# radiosonde_lite_final.net
KiCad netlist of a schematic drawn in EAGLE
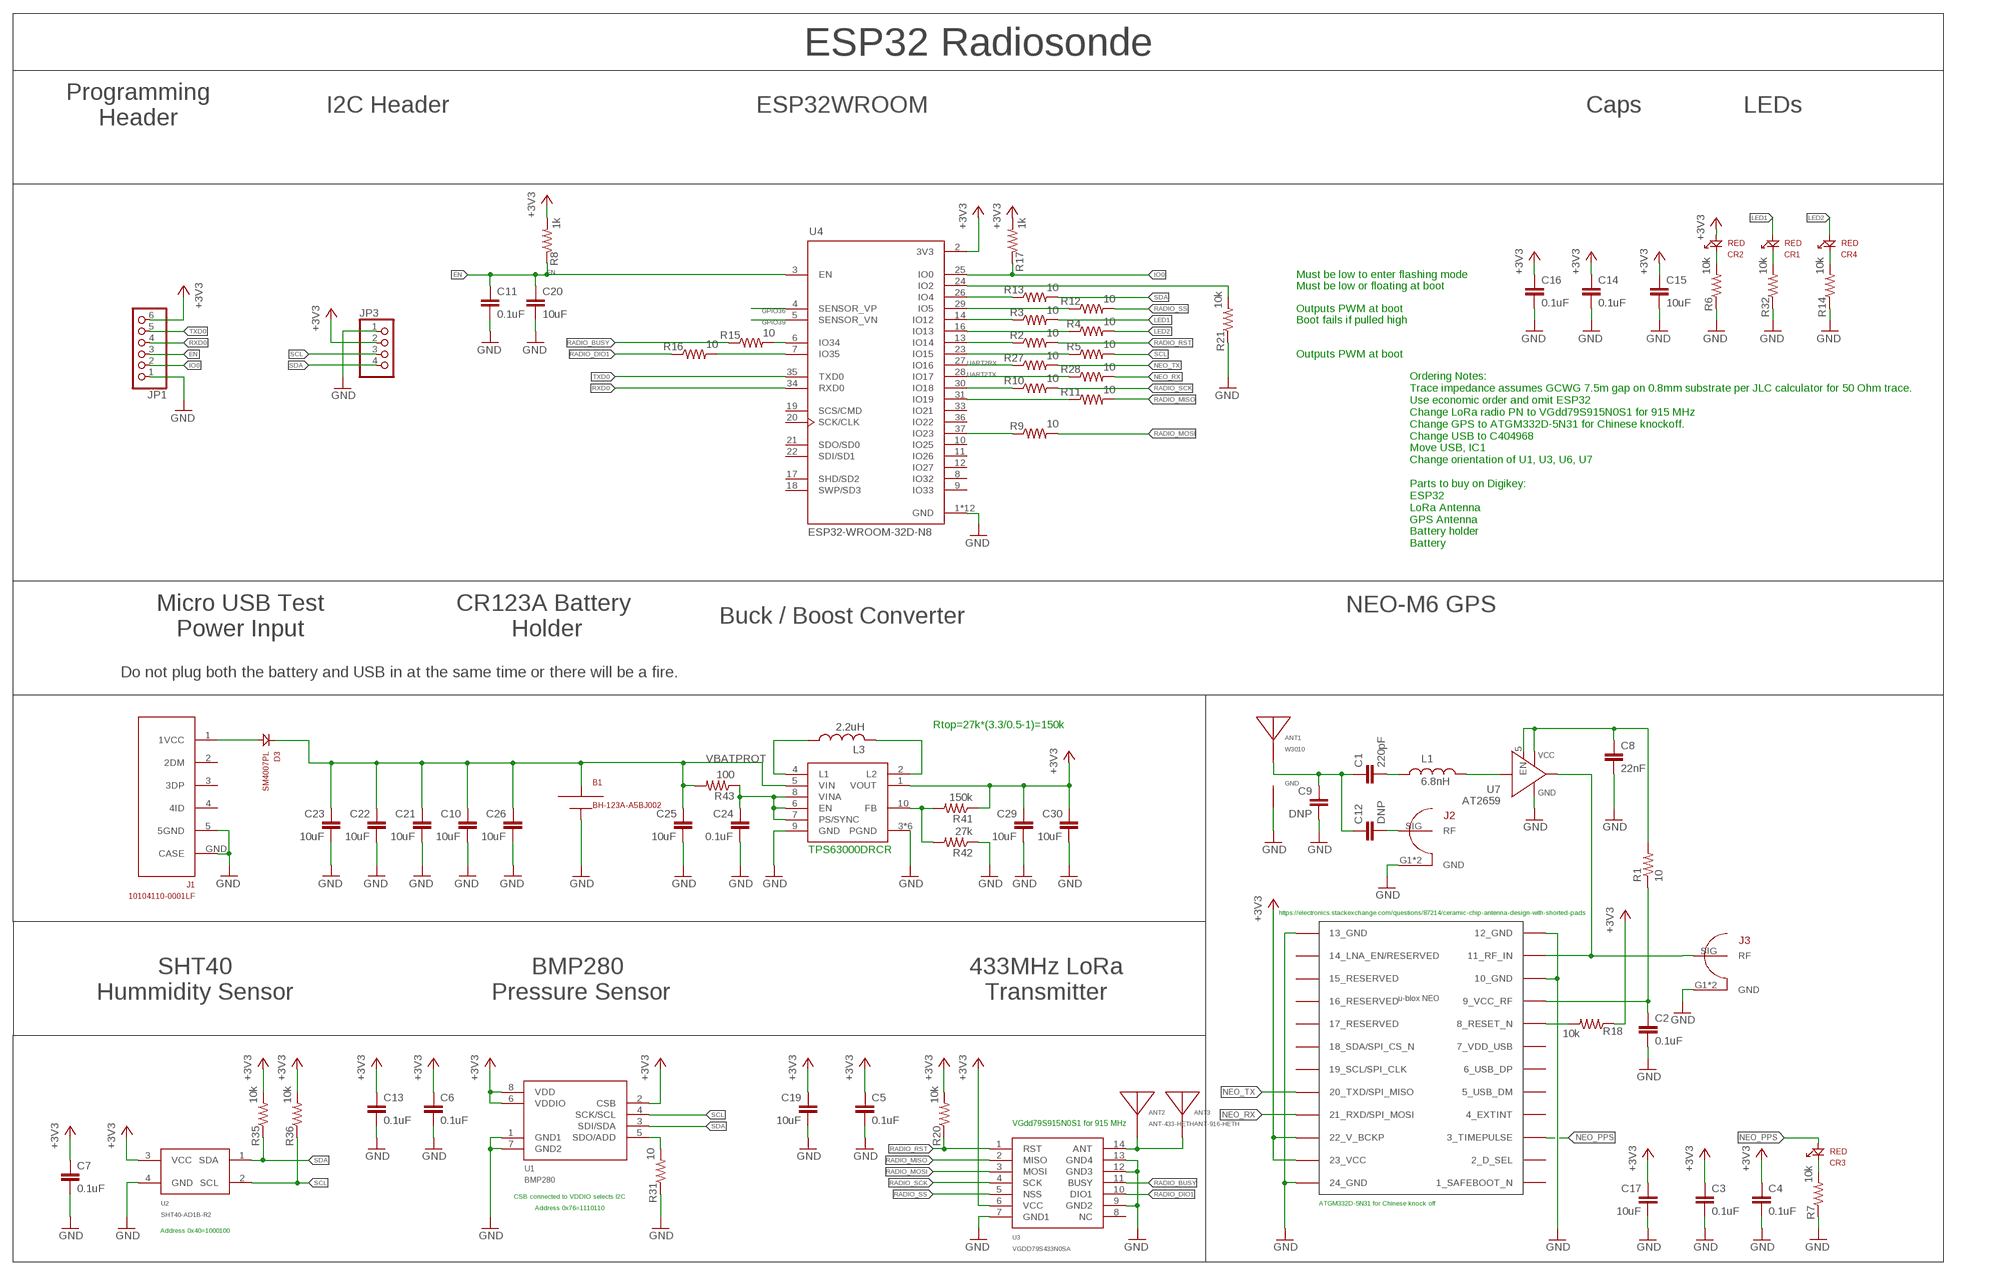
[diagram p0: schematic, sheet 1]

(export (version "E")
  (design (tool "Eeschema 10.0.6"))
  (components
    (comp (ref "ANT1")
      (value "W3010")
      (footprint "eagle-import:W3010")
      (libsource (lib "eagle-import") (part "W3010"))
    )
    (comp (ref "ANT2")
      (value "ANT-433-HETH")
      (footprint "eagle-import:ANT-433-HETH")
      (fields (field (name "PARTNO") "ANT-433-HETH-ND"))
      (libsource (lib "eagle-import") (part "ANT-433-HETH"))
    )
    (comp (ref "ANT3")
      (value "ANT-916-HETH")
      (footprint "eagle-import:ANT-916-HETH")
      (libsource (lib "eagle-import") (part "ANT-916-HETH"))
    )
    (comp (ref "B1")
      (value "BH-123A-A5BJ002")
      (footprint "eagle-import:BH-123A-A5BJ002")
      (libsource (lib "eagle-import") (part "BH-123A-A5BJ002"))
    )
    (comp (ref "C1")
      (value "220pF")
      (footprint "eagle-import:0402_INDUCTOR")
      (libsource (lib "eagle-import") (part "0402_CAPACITOR"))
    )
    (comp (ref "C2")
      (value "0.1uF")
      (footprint "eagle-import:0402_INDUCTOR")
      (libsource (lib "eagle-import") (part "0402_CAPACITOR"))
    )
    (comp (ref "C3")
      (value "0.1uF")
      (footprint "eagle-import:0402_INDUCTOR")
      (libsource (lib "eagle-import") (part "0402_CAPACITOR"))
    )
    (comp (ref "C4")
      (value "0.1uF")
      (footprint "eagle-import:0402_INDUCTOR")
      (libsource (lib "eagle-import") (part "0402_CAPACITOR"))
    )
    (comp (ref "C5")
      (value "0.1uF")
      (footprint "eagle-import:0402_INDUCTOR")
      (libsource (lib "eagle-import") (part "0402_CAPACITOR"))
    )
    (comp (ref "C6")
      (value "0.1uF")
      (footprint "eagle-import:0402_INDUCTOR")
      (libsource (lib "eagle-import") (part "0402_CAPACITOR"))
    )
    (comp (ref "C7")
      (value "0.1uF")
      (footprint "eagle-import:0402_INDUCTOR")
      (libsource (lib "eagle-import") (part "0402_CAPACITOR"))
    )
    (comp (ref "C8")
      (value "22nF")
      (footprint "eagle-import:0402_INDUCTOR")
      (libsource (lib "eagle-import") (part "0402_CAPACITOR"))
    )
    (comp (ref "C9")
      (value "DNP")
      (footprint "eagle-import:0402_INDUCTOR")
      (libsource (lib "eagle-import") (part "0402_CAPACITOR"))
    )
    (comp (ref "C10")
      (value "10uF")
      (footprint "eagle-import:0603")
      (libsource (lib "eagle-import") (part "0603_CAPACITOR"))
    )
    (comp (ref "C11")
      (value "0.1uF")
      (footprint "eagle-import:0402_INDUCTOR")
      (libsource (lib "eagle-import") (part "0402_CAPACITOR"))
    )
    (comp (ref "C12")
      (value "DNP")
      (footprint "eagle-import:0402_INDUCTOR")
      (libsource (lib "eagle-import") (part "0402_CAPACITOR"))
    )
    (comp (ref "C13")
      (value "0.1uF")
      (footprint "eagle-import:0402_INDUCTOR")
      (libsource (lib "eagle-import") (part "0402_CAPACITOR"))
    )
    (comp (ref "C14")
      (value "0.1uF")
      (footprint "eagle-import:0402_INDUCTOR")
      (libsource (lib "eagle-import") (part "0402_CAPACITOR"))
    )
    (comp (ref "C15")
      (value "10uF")
      (footprint "eagle-import:0603")
      (libsource (lib "eagle-import") (part "0603_CAPACITOR"))
    )
    (comp (ref "C16")
      (value "0.1uF")
      (footprint "eagle-import:0402_INDUCTOR")
      (libsource (lib "eagle-import") (part "0402_CAPACITOR"))
    )
    (comp (ref "C17")
      (value "10uF")
      (footprint "eagle-import:0603")
      (libsource (lib "eagle-import") (part "0603_CAPACITOR"))
    )
    (comp (ref "C19")
      (value "10uF")
      (footprint "eagle-import:0603")
      (libsource (lib "eagle-import") (part "0603_CAPACITOR"))
    )
    (comp (ref "C20")
      (value "10uF")
      (footprint "eagle-import:0603")
      (libsource (lib "eagle-import") (part "0603_CAPACITOR"))
    )
    (comp (ref "C21")
      (value "10uF")
      (footprint "eagle-import:0603")
      (libsource (lib "eagle-import") (part "0603_CAPACITOR"))
    )
    (comp (ref "C22")
      (value "10uF")
      (footprint "eagle-import:0603")
      (libsource (lib "eagle-import") (part "0603_CAPACITOR"))
    )
    (comp (ref "C23")
      (value "10uF")
      (footprint "eagle-import:0603")
      (libsource (lib "eagle-import") (part "0603_CAPACITOR"))
    )
    (comp (ref "C24")
      (value "0.1uF")
      (footprint "eagle-import:0603")
      (libsource (lib "eagle-import") (part "0603_CAPACITOR"))
    )
    (comp (ref "C25")
      (value "10uF")
      (footprint "eagle-import:0603")
      (libsource (lib "eagle-import") (part "0603_CAPACITOR"))
    )
    (comp (ref "C26")
      (value "10uF")
      (footprint "eagle-import:0603")
      (libsource (lib "eagle-import") (part "0603_CAPACITOR"))
    )
    (comp (ref "C29")
      (value "10uF")
      (footprint "eagle-import:0603")
      (libsource (lib "eagle-import") (part "0603_CAPACITOR"))
    )
    (comp (ref "C30")
      (value "10uF")
      (footprint "eagle-import:0603")
      (libsource (lib "eagle-import") (part "0603_CAPACITOR"))
    )
    (comp (ref "CR1")
      (value "RED")
      (footprint "eagle-import:0603_DIODE")
      (fields (field (name "PARTNO") "732-4978-1-ND"))
      (libsource (lib "eagle-import") (part "150060RS75000"))
    )
    (comp (ref "CR2")
      (value "RED")
      (footprint "eagle-import:0603_DIODE")
      (fields (field (name "PARTNO") "732-4978-1-ND"))
      (libsource (lib "eagle-import") (part "150060RS75000"))
    )
    (comp (ref "CR3")
      (value "RED")
      (footprint "eagle-import:0603_DIODE")
      (fields (field (name "PARTNO") "732-4978-1-ND"))
      (libsource (lib "eagle-import") (part "150060RS75000"))
    )
    (comp (ref "CR4")
      (value "RED")
      (footprint "eagle-import:0603_DIODE")
      (fields (field (name "PARTNO") "732-4978-1-ND"))
      (libsource (lib "eagle-import") (part "150060RS75000"))
    )
    (comp (ref "D3")
      (value "SM4007PL")
      (footprint "eagle-import:SOD123(AK)")
      (libsource (lib "eagle-import") (part "SM4007PL"))
    )
    (comp (ref "IC1")
      (value "NEO-M8")
      (footprint "eagle-import:NEO-M8")
      (libsource (lib "eagle-import") (part "NEO-M8"))
    )
    (comp (ref "J1")
      (value "10104110-0001LF")
      (footprint "eagle-import:MICRO_USB")
      (fields (field (name "PARTNO") "609-4052-1-ND"))
      (libsource (lib "eagle-import") (part "10104110-0001LF"))
    )
    (comp (ref "J2")
      (value "CONUFL001-SMD")
      (footprint "eagle-import:U.FL")
      (libsource (lib "eagle-import") (part "CONUFL001-SMD"))
    )
    (comp (ref "J3")
      (value "CONUFL001-SMD")
      (footprint "eagle-import:U.FL")
      (libsource (lib "eagle-import") (part "CONUFL001-SMD"))
    )
    (comp (ref "JP1")
      (value "PINHD-1X6")
      (footprint "eagle-import:1X06")
      (libsource (lib "eagle-import") (part "PINHD-1X6"))
    )
    (comp (ref "JP3")
      (value "PINHD-1X4")
      (footprint "eagle-import:1X04")
      (libsource (lib "eagle-import") (part "PINHD-1X4"))
    )
    (comp (ref "L1")
      (value "6.8nH")
      (footprint "eagle-import:0402_INDUCTOR")
      (libsource (lib "eagle-import") (part "0402_INDUCTOR"))
    )
    (comp (ref "L3")
      (value "2.2uH")
      (footprint "eagle-import:CY43")
      (libsource (lib "eagle-import") (part "CY43-2.2UH"))
    )
    (comp (ref "R1")
      (value "10")
      (footprint "eagle-import:R0402")
      (libsource (lib "eagle-import") (part "0402_RESISTOR"))
    )
    (comp (ref "R2")
      (value "10")
      (footprint "eagle-import:R0402")
      (libsource (lib "eagle-import") (part "0402_RESISTOR"))
    )
    (comp (ref "R3")
      (value "10")
      (footprint "eagle-import:R0402")
      (libsource (lib "eagle-import") (part "0402_RESISTOR"))
    )
    (comp (ref "R4")
      (value "10")
      (footprint "eagle-import:R0402")
      (libsource (lib "eagle-import") (part "0402_RESISTOR"))
    )
    (comp (ref "R5")
      (value "10")
      (footprint "eagle-import:R0402")
      (libsource (lib "eagle-import") (part "0402_RESISTOR"))
    )
    (comp (ref "R6")
      (value "10k")
      (footprint "eagle-import:R0402")
      (libsource (lib "eagle-import") (part "0402_RESISTOR"))
    )
    (comp (ref "R7")
      (value "10k")
      (footprint "eagle-import:R0402")
      (libsource (lib "eagle-import") (part "0402_RESISTOR"))
    )
    (comp (ref "R8")
      (value "1k")
      (footprint "eagle-import:R0402")
      (libsource (lib "eagle-import") (part "0402_RESISTOR"))
    )
    (comp (ref "R9")
      (value "10")
      (footprint "eagle-import:R0402")
      (libsource (lib "eagle-import") (part "0402_RESISTOR"))
    )
    (comp (ref "R10")
      (value "10")
      (footprint "eagle-import:R0402")
      (libsource (lib "eagle-import") (part "0402_RESISTOR"))
    )
    (comp (ref "R11")
      (value "10")
      (footprint "eagle-import:R0402")
      (libsource (lib "eagle-import") (part "0402_RESISTOR"))
    )
    (comp (ref "R12")
      (value "10")
      (footprint "eagle-import:R0402")
      (libsource (lib "eagle-import") (part "0402_RESISTOR"))
    )
    (comp (ref "R13")
      (value "10")
      (footprint "eagle-import:R0402")
      (libsource (lib "eagle-import") (part "0402_RESISTOR"))
    )
    (comp (ref "R14")
      (value "10k")
      (footprint "eagle-import:R0402")
      (libsource (lib "eagle-import") (part "0402_RESISTOR"))
    )
    (comp (ref "R15")
      (value "10")
      (footprint "eagle-import:R0402")
      (libsource (lib "eagle-import") (part "0402_RESISTOR"))
    )
    (comp (ref "R16")
      (value "10")
      (footprint "eagle-import:R0402")
      (libsource (lib "eagle-import") (part "0402_RESISTOR"))
    )
    (comp (ref "R17")
      (value "1k")
      (footprint "eagle-import:R0402")
      (libsource (lib "eagle-import") (part "0402_RESISTOR"))
    )
    (comp (ref "R18")
      (value "10k")
      (footprint "eagle-import:R0402")
      (libsource (lib "eagle-import") (part "0402_RESISTOR"))
    )
    (comp (ref "R20")
      (value "10k")
      (footprint "eagle-import:R0402")
      (libsource (lib "eagle-import") (part "0402_RESISTOR"))
    )
    (comp (ref "R21")
      (value "10k")
      (footprint "eagle-import:R0402")
      (libsource (lib "eagle-import") (part "0402_RESISTOR"))
    )
    (comp (ref "R27")
      (value "10")
      (footprint "eagle-import:R0402")
      (libsource (lib "eagle-import") (part "0402_RESISTOR"))
    )
    (comp (ref "R28")
      (value "10")
      (footprint "eagle-import:R0402")
      (libsource (lib "eagle-import") (part "0402_RESISTOR"))
    )
    (comp (ref "R31")
      (value "10")
      (footprint "eagle-import:R0402")
      (libsource (lib "eagle-import") (part "0402_RESISTOR"))
    )
    (comp (ref "R32")
      (value "10k")
      (footprint "eagle-import:R0402")
      (libsource (lib "eagle-import") (part "0402_RESISTOR"))
    )
    (comp (ref "R35")
      (value "10k")
      (footprint "eagle-import:R0402")
      (libsource (lib "eagle-import") (part "0402_RESISTOR"))
    )
    (comp (ref "R36")
      (value "10k")
      (footprint "eagle-import:R0402")
      (libsource (lib "eagle-import") (part "0402_RESISTOR"))
    )
    (comp (ref "R41")
      (value "150k")
      (footprint "eagle-import:0603")
      (libsource (lib "eagle-import") (part "0603_RESISTOR"))
    )
    (comp (ref "R42")
      (value "27k")
      (footprint "eagle-import:0603")
      (libsource (lib "eagle-import") (part "0603_RESISTOR"))
    )
    (comp (ref "R43")
      (value "100")
      (footprint "eagle-import:0603")
      (libsource (lib "eagle-import") (part "0603_RESISTOR"))
    )
    (comp (ref "U1")
      (value "BMP280")
      (footprint "eagle-import:BME280")
      (fields (field (name "PARTNO") "828-1064-1-ND"))
      (libsource (lib "eagle-import") (part "BMP280"))
    )
    (comp (ref "U2")
      (value "SHT40-AD1B-R2")
      (footprint "eagle-import:SHT40")
      (libsource (lib "eagle-import") (part "SHT40-AD1B-R2"))
    )
    (comp (ref "U3")
      (value "VGDD79S433N0SA")
      (footprint "eagle-import:VGDD79S433N0SA")
      (libsource (lib "eagle-import") (part "VGDD79S433N0SA"))
    )
    (comp (ref "U4")
      (value "ESP32-WROOM-32D-N8")
      (footprint "eagle-import:MODULE_ESP32-WROOM-32D")
      (fields (field (name "MF") "Espressif Systems") (field (name "MP") "ESP32-WROOM-32D"))
      (libsource (lib "eagle-import") (part "ESP32-WROOM-32D"))
    )
    (comp (ref "U6")
      (value "TPS63000DRCR")
      (footprint "eagle-import:S-PVSON-N10")
      (fields (field (name "PARTNO") "296-19641-1-ND"))
      (libsource (lib "eagle-import") (part "TPS63000DRCR"))
    )
    (comp (ref "U7")
      (value "AT2659")
      (footprint "eagle-import:6DFN-1X1.6")
      (libsource (lib "eagle-import") (part "AT2659"))
    )
  )
  (nets
    (net (code "1") (name "+3V3") (class "Default")
      (node (ref "C13") (pin "P$1") (pinfunction "1_P$1") (pintype "passive"))
      (node (ref "C14") (pin "P$1") (pinfunction "1_P$1") (pintype "passive"))
      (node (ref "C15") (pin "1") (pinfunction "1_1") (pintype "passive"))
      (node (ref "C16") (pin "P$1") (pinfunction "1_P$1") (pintype "passive"))
      (node (ref "C17") (pin "1") (pinfunction "1_1") (pintype "passive"))
      (node (ref "C19") (pin "1") (pinfunction "1_1") (pintype "passive"))
      (node (ref "C29") (pin "1") (pinfunction "1_1") (pintype "passive"))
      (node (ref "C3") (pin "P$1") (pinfunction "1_P$1") (pintype "passive"))
      (node (ref "C30") (pin "1") (pinfunction "1_1") (pintype "passive"))
      (node (ref "C4") (pin "P$1") (pinfunction "1_P$1") (pintype "passive"))
      (node (ref "C5") (pin "P$1") (pinfunction "1_P$1") (pintype "passive"))
      (node (ref "C6") (pin "P$1") (pinfunction "1_P$1") (pintype "passive"))
      (node (ref "C7") (pin "P$1") (pinfunction "1_P$1") (pintype "passive"))
      (node (ref "CR2") (pin "A") (pinfunction "A_A") (pintype "bidirectional"))
      (node (ref "IC1") (pin "22") (pinfunction "22_V_BCKP_22") (pintype "bidirectional"))
      (node (ref "IC1") (pin "23") (pinfunction "23_VCC_23") (pintype "bidirectional"))
      (node (ref "JP1") (pin "6") (pinfunction "6_6") (pintype "passive"))
      (node (ref "JP3") (pin "2") (pinfunction "2_2") (pintype "passive"))
      (node (ref "R17") (pin "2") (pinfunction "2_2") (pintype "passive"))
      (node (ref "R18") (pin "1") (pinfunction "1_1") (pintype "passive"))
      (node (ref "R20") (pin "2") (pinfunction "2_2") (pintype "passive"))
      (node (ref "R35") (pin "2") (pinfunction "2_2") (pintype "passive"))
      (node (ref "R36") (pin "2") (pinfunction "2_2") (pintype "passive"))
      (node (ref "R41") (pin "1") (pinfunction "1_1") (pintype "passive"))
      (node (ref "R8") (pin "2") (pinfunction "2_2") (pintype "passive"))
      (node (ref "U1") (pin "2") (pinfunction "CSB_2") (pintype "bidirectional"))
      (node (ref "U1") (pin "6") (pinfunction "VDDIO_6") (pintype "bidirectional"))
      (node (ref "U1") (pin "8") (pinfunction "VDD_8") (pintype "bidirectional"))
      (node (ref "U2") (pin "3") (pinfunction "VCC_3") (pintype "bidirectional"))
      (node (ref "U3") (pin "6") (pinfunction "VCC_6") (pintype "bidirectional"))
      (node (ref "U4") (pin "2") (pinfunction "3V3_2") (pintype "power_in"))
      (node (ref "U6") (pin "1") (pinfunction "VOUT_1") (pintype "bidirectional"))
    )
    (net (code "2") (name "/GPIO36") (class "Default")
      (node (ref "U4") (pin "4") (pinfunction "SENSOR_VP_4") (pintype "input"))
    )
    (net (code "3") (name "/GPIO39") (class "Default")
      (node (ref "U4") (pin "5") (pinfunction "SENSOR_VN_5") (pintype "input"))
    )
    (net (code "4") (name "/UART2RX") (class "Default")
      (node (ref "R27") (pin "1") (pinfunction "1_1") (pintype "passive"))
      (node (ref "U4") (pin "27") (pinfunction "IO16_27") (pintype "bidirectional"))
    )
    (net (code "5") (name "/UART2TX") (class "Default")
      (node (ref "R28") (pin "1") (pinfunction "1_1") (pintype "passive"))
      (node (ref "U4") (pin "28") (pinfunction "IO17_28") (pintype "bidirectional"))
    )
    (net (code "6") (name "/VBATPROT") (class "Default")
      (node (ref "B1") (pin "P") (pinfunction "+_P") (pintype "bidirectional"))
      (node (ref "C10") (pin "1") (pinfunction "1_1") (pintype "passive"))
      (node (ref "C21") (pin "1") (pinfunction "1_1") (pintype "passive"))
      (node (ref "C22") (pin "1") (pinfunction "1_1") (pintype "passive"))
      (node (ref "C23") (pin "1") (pinfunction "1_1") (pintype "passive"))
      (node (ref "C25") (pin "1") (pinfunction "1_1") (pintype "passive"))
      (node (ref "C26") (pin "1") (pinfunction "1_1") (pintype "passive"))
      (node (ref "D3") (pin "K") (pinfunction "K_K") (pintype "bidirectional"))
      (node (ref "R43") (pin "2") (pinfunction "2_2") (pintype "passive"))
      (node (ref "U6") (pin "5") (pinfunction "VIN_5") (pintype "bidirectional"))
    )
    (net (code "7") (name "EN") (class "Default")
      (node (ref "C11") (pin "P$1") (pinfunction "1_P$1") (pintype "passive"))
      (node (ref "C20") (pin "1") (pinfunction "1_1") (pintype "passive"))
      (node (ref "JP1") (pin "3") (pinfunction "3_3") (pintype "passive"))
      (node (ref "R8") (pin "1") (pinfunction "1_1") (pintype "passive"))
      (node (ref "U4") (pin "3") (pinfunction "EN_3") (pintype "input"))
    )
    (net (code "8") (name "GND") (class "Default")
      (node (ref "ANT1") (pin "P$1") (pinfunction "GND_P$1") (pintype "bidirectional"))
      (node (ref "ANT1") (pin "P$3") (pinfunction "GND_P$3") (pintype "bidirectional"))
      (node (ref "B1") (pin "N") (pinfunction "-_N") (pintype "bidirectional"))
      (node (ref "C10") (pin "2") (pinfunction "2_2") (pintype "passive"))
      (node (ref "C11") (pin "P$2") (pinfunction "2_P$2") (pintype "passive"))
      (node (ref "C13") (pin "P$2") (pinfunction "2_P$2") (pintype "passive"))
      (node (ref "C14") (pin "P$2") (pinfunction "2_P$2") (pintype "passive"))
      (node (ref "C15") (pin "2") (pinfunction "2_2") (pintype "passive"))
      (node (ref "C16") (pin "P$2") (pinfunction "2_P$2") (pintype "passive"))
      (node (ref "C17") (pin "2") (pinfunction "2_2") (pintype "passive"))
      (node (ref "C19") (pin "2") (pinfunction "2_2") (pintype "passive"))
      (node (ref "C2") (pin "P$2") (pinfunction "2_P$2") (pintype "passive"))
      (node (ref "C20") (pin "2") (pinfunction "2_2") (pintype "passive"))
      (node (ref "C21") (pin "2") (pinfunction "2_2") (pintype "passive"))
      (node (ref "C22") (pin "2") (pinfunction "2_2") (pintype "passive"))
      (node (ref "C23") (pin "2") (pinfunction "2_2") (pintype "passive"))
      (node (ref "C24") (pin "2") (pinfunction "2_2") (pintype "passive"))
      (node (ref "C25") (pin "2") (pinfunction "2_2") (pintype "passive"))
      (node (ref "C26") (pin "2") (pinfunction "2_2") (pintype "passive"))
      (node (ref "C29") (pin "2") (pinfunction "2_2") (pintype "passive"))
      (node (ref "C3") (pin "P$2") (pinfunction "2_P$2") (pintype "passive"))
      (node (ref "C30") (pin "2") (pinfunction "2_2") (pintype "passive"))
      (node (ref "C4") (pin "P$2") (pinfunction "2_P$2") (pintype "passive"))
      (node (ref "C5") (pin "P$2") (pinfunction "2_P$2") (pintype "passive"))
      (node (ref "C6") (pin "P$2") (pinfunction "2_P$2") (pintype "passive"))
      (node (ref "C7") (pin "P$2") (pinfunction "2_P$2") (pintype "passive"))
      (node (ref "C8") (pin "P$2") (pinfunction "2_P$2") (pintype "passive"))
      (node (ref "C9") (pin "P$2") (pinfunction "2_P$2") (pintype "passive"))
      (node (ref "IC1") (pin "10") (pinfunction "10_GND_10") (pintype "bidirectional"))
      (node (ref "IC1") (pin "12") (pinfunction "12_GND_12") (pintype "bidirectional"))
      (node (ref "IC1") (pin "13") (pinfunction "13_GND_13") (pintype "bidirectional"))
      (node (ref "IC1") (pin "24") (pinfunction "24_GND_24") (pintype "bidirectional"))
      (node (ref "J1") (pin "5") (pinfunction "5GND_5") (pintype "bidirectional"))
      (node (ref "J1") (pin "GND") (pinfunction "CASE_GND") (pintype "bidirectional"))
      (node (ref "J2") (pin "G1") (pinfunction "GND_G1") (pintype "bidirectional"))
      (node (ref "J2") (pin "G2") (pinfunction "GND_G2") (pintype "bidirectional"))
      (node (ref "J3") (pin "G1") (pinfunction "GND_G1") (pintype "bidirectional"))
      (node (ref "J3") (pin "G2") (pinfunction "GND_G2") (pintype "bidirectional"))
      (node (ref "JP1") (pin "1") (pinfunction "1_1") (pintype "passive"))
      (node (ref "JP3") (pin "1") (pinfunction "1_1") (pintype "passive"))
      (node (ref "R14") (pin "1") (pinfunction "1_1") (pintype "passive"))
      (node (ref "R21") (pin "1") (pinfunction "1_1") (pintype "passive"))
      (node (ref "R31") (pin "1") (pinfunction "1_1") (pintype "passive"))
      (node (ref "R32") (pin "1") (pinfunction "1_1") (pintype "passive"))
      (node (ref "R42") (pin "1") (pinfunction "1_1") (pintype "passive"))
      (node (ref "R6") (pin "1") (pinfunction "1_1") (pintype "passive"))
      (node (ref "R7") (pin "1") (pinfunction "1_1") (pintype "passive"))
      (node (ref "U1") (pin "1") (pinfunction "GND1_1") (pintype "bidirectional"))
      (node (ref "U1") (pin "7") (pinfunction "GND2_7") (pintype "bidirectional"))
      (node (ref "U2") (pin "4") (pinfunction "GND_4") (pintype "bidirectional"))
      (node (ref "U3") (pin "12") (pinfunction "GND3_12") (pintype "bidirectional"))
      (node (ref "U3") (pin "13") (pinfunction "GND4_13") (pintype "bidirectional"))
      (node (ref "U3") (pin "7") (pinfunction "GND1_7") (pintype "bidirectional"))
      (node (ref "U3") (pin "9") (pinfunction "GND2_9") (pintype "bidirectional"))
      (node (ref "U4") (pin "1") (pinfunction "GND_1") (pintype "power_in"))
      (node (ref "U4") (pin "15") (pinfunction "GND_15") (pintype "power_in"))
      (node (ref "U4") (pin "38") (pinfunction "GND_38") (pintype "power_in"))
      (node (ref "U4") (pin "39_1") (pinfunction "GND_39_1") (pintype "power_in"))
      (node (ref "U4") (pin "39_2") (pinfunction "GND_39_2") (pintype "power_in"))
      (node (ref "U4") (pin "39_3") (pinfunction "GND_39_3") (pintype "power_in"))
      (node (ref "U4") (pin "39_4") (pinfunction "GND_39_4") (pintype "power_in"))
      (node (ref "U4") (pin "39_5") (pinfunction "GND_39_5") (pintype "power_in"))
      (node (ref "U4") (pin "39_6") (pinfunction "GND_39_6") (pintype "power_in"))
      (node (ref "U4") (pin "39_7") (pinfunction "GND_39_7") (pintype "power_in"))
      (node (ref "U4") (pin "39_8") (pinfunction "GND_39_8") (pintype "power_in"))
      (node (ref "U4") (pin "39_9") (pinfunction "GND_39_9") (pintype "power_in"))
      (node (ref "U6") (pin "3") (pinfunction "PGND_3") (pintype "bidirectional"))
      (node (ref "U6") (pin "9") (pinfunction "GND_9") (pintype "bidirectional"))
      (node (ref "U6") (pin "PG") (pinfunction "PGND_PG") (pintype "bidirectional"))
      (node (ref "U6") (pin "PG1") (pinfunction "PGND_PG1") (pintype "bidirectional"))
      (node (ref "U6") (pin "PG2") (pinfunction "PGND_PG2") (pintype "bidirectional"))
      (node (ref "U6") (pin "PG3") (pinfunction "PGND_PG3") (pintype "bidirectional"))
      (node (ref "U6") (pin "PG4") (pinfunction "PGND_PG4") (pintype "bidirectional"))
      (node (ref "U7") (pin "1") (pinfunction "GND_1") (pintype "bidirectional"))
      (node (ref "U7") (pin "2") (pinfunction "GND_2") (pintype "bidirectional"))
    )
    (net (code "9") (name "IO0") (class "Default")
      (node (ref "JP1") (pin "2") (pinfunction "2_2") (pintype "passive"))
      (node (ref "R17") (pin "1") (pinfunction "1_1") (pintype "passive"))
      (node (ref "U4") (pin "25") (pinfunction "IO0_25") (pintype "bidirectional"))
    )
    (net (code "10") (name "LED1") (class "Default")
      (node (ref "CR1") (pin "A") (pinfunction "A_A") (pintype "bidirectional"))
      (node (ref "R3") (pin "2") (pinfunction "2_2") (pintype "passive"))
    )
    (net (code "11") (name "LED2") (class "Default")
      (node (ref "CR4") (pin "A") (pinfunction "A_A") (pintype "bidirectional"))
      (node (ref "R4") (pin "2") (pinfunction "2_2") (pintype "passive"))
    )
    (net (code "12") (name "NEO_PPS") (class "Default")
      (node (ref "CR3") (pin "A") (pinfunction "A_A") (pintype "bidirectional"))
      (node (ref "IC1") (pin "3") (pinfunction "3_TIMEPULSE_3") (pintype "bidirectional"))
    )
    (net (code "13") (name "NEO_RX") (class "Default")
      (node (ref "IC1") (pin "21") (pinfunction "21_RXD/SPI_MOSI_21") (pintype "bidirectional"))
      (node (ref "R28") (pin "2") (pinfunction "2_2") (pintype "passive"))
    )
    (net (code "14") (name "NEO_TX") (class "Default")
      (node (ref "IC1") (pin "20") (pinfunction "20_TXD/SPI_MISO_20") (pintype "bidirectional"))
      (node (ref "R27") (pin "2") (pinfunction "2_2") (pintype "passive"))
    )
    (net (code "15") (name "Net-(ANT1-ANT)") (class "Default")
      (node (ref "ANT1") (pin "P$2") (pinfunction "ANT_P$2") (pintype "bidirectional"))
      (node (ref "C1") (pin "P$1") (pinfunction "1_P$1") (pintype "passive"))
      (node (ref "C12") (pin "P$1") (pinfunction "1_P$1") (pintype "passive"))
      (node (ref "C9") (pin "P$1") (pinfunction "1_P$1") (pintype "passive"))
    )
    (net (code "16") (name "Net-(ANT3-P$1)") (class "Default")
      (node (ref "ANT2") (pin "IN1") (pinfunction "P$1_IN1") (pintype "bidirectional"))
      (node (ref "ANT2") (pin "IN2") (pinfunction "P$1_IN2") (pintype "bidirectional"))
      (node (ref "ANT3") (pin "IN1") (pinfunction "P$1_IN1") (pintype "bidirectional"))
      (node (ref "U3") (pin "14") (pinfunction "ANT_14") (pintype "bidirectional"))
    )
    (net (code "17") (name "Net-(C1-2)") (class "Default")
      (node (ref "C1") (pin "P$2") (pinfunction "2_P$2") (pintype "passive"))
      (node (ref "L1") (pin "P$1") (pinfunction "P$1_P$1") (pintype "bidirectional"))
    )
    (net (code "18") (name "Net-(C2-1)") (class "Default")
      (node (ref "C2") (pin "P$1") (pinfunction "1_P$1") (pintype "passive"))
      (node (ref "IC1") (pin "9") (pinfunction "9_VCC_RF_9") (pintype "bidirectional"))
      (node (ref "R1") (pin "1") (pinfunction "1_1") (pintype "passive"))
    )
    (net (code "19") (name "Net-(C8-1)") (class "Default")
      (node (ref "C8") (pin "P$1") (pinfunction "1_P$1") (pintype "passive"))
      (node (ref "R1") (pin "2") (pinfunction "2_2") (pintype "passive"))
      (node (ref "U7") (pin "4") (pinfunction "VS_4") (pintype "bidirectional"))
      (node (ref "U7") (pin "5") (pinfunction "EN_5") (pintype "bidirectional"))
    )
    (net (code "20") (name "Net-(C12-2)") (class "Default")
      (node (ref "C12") (pin "P$2") (pinfunction "2_P$2") (pintype "passive"))
      (node (ref "J2") (pin "SIG") (pinfunction "RF_SIG") (pintype "bidirectional"))
    )
    (net (code "21") (name "Net-(CR1-PadK)") (class "Default")
      (node (ref "CR1") (pin "K") (pinfunction "K_K") (pintype "bidirectional"))
      (node (ref "R32") (pin "2") (pinfunction "2_2") (pintype "passive"))
    )
    (net (code "22") (name "Net-(CR2-PadK)") (class "Default")
      (node (ref "CR2") (pin "K") (pinfunction "K_K") (pintype "bidirectional"))
      (node (ref "R6") (pin "2") (pinfunction "2_2") (pintype "passive"))
    )
    (net (code "23") (name "Net-(CR3-PadK)") (class "Default")
      (node (ref "CR3") (pin "K") (pinfunction "K_K") (pintype "bidirectional"))
      (node (ref "R7") (pin "2") (pinfunction "2_2") (pintype "passive"))
    )
    (net (code "24") (name "Net-(CR4-PadK)") (class "Default")
      (node (ref "CR4") (pin "K") (pinfunction "K_K") (pintype "bidirectional"))
      (node (ref "R14") (pin "2") (pinfunction "2_2") (pintype "passive"))
    )
    (net (code "25") (name "Net-(IC1-8_RESET_N)") (class "Default")
      (node (ref "IC1") (pin "8") (pinfunction "8_RESET_N_8") (pintype "bidirectional"))
      (node (ref "R18") (pin "2") (pinfunction "2_2") (pintype "passive"))
    )
    (net (code "26") (name "Net-(IC1-11_RF_IN)") (class "Default")
      (node (ref "IC1") (pin "11") (pinfunction "11_RF_IN_11") (pintype "bidirectional"))
      (node (ref "J3") (pin "SIG") (pinfunction "RF_SIG") (pintype "bidirectional"))
      (node (ref "U7") (pin "6") (pinfunction "RF_OUT_6") (pintype "bidirectional"))
    )
    (net (code "27") (name "Net-(J1-1VCC)") (class "Default")
      (node (ref "D3") (pin "A") (pinfunction "A_A") (pintype "bidirectional"))
      (node (ref "J1") (pin "1") (pinfunction "1VCC_1") (pintype "bidirectional"))
    )
    (net (code "28") (name "Net-(L3-1)") (class "Default")
      (node (ref "L3") (pin "P$1") (pinfunction "1_P$1") (pintype "passive"))
      (node (ref "U6") (pin "4") (pinfunction "L1_4") (pintype "bidirectional"))
    )
    (net (code "29") (name "Net-(L3-2)") (class "Default")
      (node (ref "L3") (pin "P$2") (pinfunction "2_P$2") (pintype "passive"))
      (node (ref "U6") (pin "2") (pinfunction "L2_2") (pintype "bidirectional"))
    )
    (net (code "30") (name "Net-(U1-SDO{slash}ADD)") (class "Default")
      (node (ref "R31") (pin "2") (pinfunction "2_2") (pintype "passive"))
      (node (ref "U1") (pin "5") (pinfunction "SDO/ADD_5") (pintype "bidirectional"))
    )
    (net (code "31") (name "Net-(U4-IO2)") (class "Default")
      (node (ref "R21") (pin "2") (pinfunction "2_2") (pintype "passive"))
      (node (ref "U4") (pin "24") (pinfunction "IO2_24") (pintype "bidirectional"))
    )
    (net (code "32") (name "Net-(U4-IO4)") (class "Default")
      (node (ref "R13") (pin "1") (pinfunction "1_1") (pintype "passive"))
      (node (ref "U4") (pin "26") (pinfunction "IO4_26") (pintype "bidirectional"))
    )
    (net (code "33") (name "Net-(U4-IO5)") (class "Default")
      (node (ref "R12") (pin "1") (pinfunction "1_1") (pintype "passive"))
      (node (ref "U4") (pin "29") (pinfunction "IO5_29") (pintype "bidirectional"))
    )
    (net (code "34") (name "Net-(U4-IO12)") (class "Default")
      (node (ref "R3") (pin "1") (pinfunction "1_1") (pintype "passive"))
      (node (ref "U4") (pin "14") (pinfunction "IO12_14") (pintype "bidirectional"))
    )
    (net (code "35") (name "Net-(U4-IO13)") (class "Default")
      (node (ref "R4") (pin "1") (pinfunction "1_1") (pintype "passive"))
      (node (ref "U4") (pin "16") (pinfunction "IO13_16") (pintype "bidirectional"))
    )
    (net (code "36") (name "Net-(U4-IO14)") (class "Default")
      (node (ref "R2") (pin "1") (pinfunction "1_1") (pintype "passive"))
      (node (ref "U4") (pin "13") (pinfunction "IO14_13") (pintype "bidirectional"))
    )
    (net (code "37") (name "Net-(U4-IO15)") (class "Default")
      (node (ref "R5") (pin "1") (pinfunction "1_1") (pintype "passive"))
      (node (ref "U4") (pin "23") (pinfunction "IO15_23") (pintype "bidirectional"))
    )
    (net (code "38") (name "Net-(U4-IO18)") (class "Default")
      (node (ref "R10") (pin "1") (pinfunction "1_1") (pintype "passive"))
      (node (ref "U4") (pin "30") (pinfunction "IO18_30") (pintype "bidirectional"))
    )
    (net (code "39") (name "Net-(U4-IO19)") (class "Default")
      (node (ref "R11") (pin "1") (pinfunction "1_1") (pintype "passive"))
      (node (ref "U4") (pin "31") (pinfunction "IO19_31") (pintype "bidirectional"))
    )
    (net (code "40") (name "Net-(U4-IO23)") (class "Default")
      (node (ref "R9") (pin "1") (pinfunction "1_1") (pintype "passive"))
      (node (ref "U4") (pin "37") (pinfunction "IO23_37") (pintype "bidirectional"))
    )
    (net (code "41") (name "Net-(U4-IO34)") (class "Default")
      (node (ref "R15") (pin "2") (pinfunction "2_2") (pintype "passive"))
      (node (ref "U4") (pin "6") (pinfunction "IO34_6") (pintype "input"))
    )
    (net (code "42") (name "Net-(U4-IO35)") (class "Default")
      (node (ref "R16") (pin "2") (pinfunction "2_2") (pintype "passive"))
      (node (ref "U4") (pin "7") (pinfunction "IO35_7") (pintype "input"))
    )
    (net (code "43") (name "Net-(U6-EN)") (class "Default")
      (node (ref "C24") (pin "1") (pinfunction "1_1") (pintype "passive"))
      (node (ref "R43") (pin "1") (pinfunction "1_1") (pintype "passive"))
      (node (ref "U6") (pin "6") (pinfunction "EN_6") (pintype "bidirectional"))
      (node (ref "U6") (pin "7") (pinfunction "PS/SYNC_7") (pintype "bidirectional"))
      (node (ref "U6") (pin "8") (pinfunction "VINA_8") (pintype "bidirectional"))
    )
    (net (code "44") (name "Net-(U6-FB)") (class "Default")
      (node (ref "R41") (pin "2") (pinfunction "2_2") (pintype "passive"))
      (node (ref "R42") (pin "2") (pinfunction "2_2") (pintype "passive"))
      (node (ref "U6") (pin "10") (pinfunction "FB_10") (pintype "bidirectional"))
    )
    (net (code "45") (name "Net-(U7-RF_IN)") (class "Default")
      (node (ref "L1") (pin "P$2") (pinfunction "P$2_P$2") (pintype "bidirectional"))
      (node (ref "U7") (pin "3") (pinfunction "RF_IN_3") (pintype "bidirectional"))
    )
    (net (code "46") (name "RADIO_BUSY") (class "Default")
      (node (ref "R15") (pin "1") (pinfunction "1_1") (pintype "passive"))
      (node (ref "U3") (pin "11") (pinfunction "BUSY_11") (pintype "bidirectional"))
    )
    (net (code "47") (name "RADIO_DIO1") (class "Default")
      (node (ref "R16") (pin "1") (pinfunction "1_1") (pintype "passive"))
      (node (ref "U3") (pin "10") (pinfunction "DIO1_10") (pintype "bidirectional"))
    )
    (net (code "48") (name "RADIO_MISO") (class "Default")
      (node (ref "R11") (pin "2") (pinfunction "2_2") (pintype "passive"))
      (node (ref "U3") (pin "2") (pinfunction "MISO_2") (pintype "bidirectional"))
    )
    (net (code "49") (name "RADIO_MOSI") (class "Default")
      (node (ref "R9") (pin "2") (pinfunction "2_2") (pintype "passive"))
      (node (ref "U3") (pin "3") (pinfunction "MOSI_3") (pintype "bidirectional"))
    )
    (net (code "50") (name "RADIO_RST") (class "Default")
      (node (ref "R2") (pin "2") (pinfunction "2_2") (pintype "passive"))
      (node (ref "R20") (pin "1") (pinfunction "1_1") (pintype "passive"))
      (node (ref "U3") (pin "1") (pinfunction "RST_1") (pintype "bidirectional"))
    )
    (net (code "51") (name "RADIO_SCK") (class "Default")
      (node (ref "R10") (pin "2") (pinfunction "2_2") (pintype "passive"))
      (node (ref "U3") (pin "4") (pinfunction "SCK_4") (pintype "bidirectional"))
    )
    (net (code "52") (name "RADIO_SS") (class "Default")
      (node (ref "R12") (pin "2") (pinfunction "2_2") (pintype "passive"))
      (node (ref "U3") (pin "5") (pinfunction "NSS_5") (pintype "bidirectional"))
    )
    (net (code "53") (name "RXD0") (class "Default")
      (node (ref "JP1") (pin "4") (pinfunction "4_4") (pintype "passive"))
      (node (ref "U4") (pin "34") (pinfunction "RXD0_34") (pintype "bidirectional"))
    )
    (net (code "54") (name "SCL") (class "Default")
      (node (ref "JP3") (pin "3") (pinfunction "3_3") (pintype "passive"))
      (node (ref "R36") (pin "1") (pinfunction "1_1") (pintype "passive"))
      (node (ref "R5") (pin "2") (pinfunction "2_2") (pintype "passive"))
      (node (ref "U1") (pin "4") (pinfunction "SCK/SCL_4") (pintype "bidirectional"))
      (node (ref "U2") (pin "2") (pinfunction "SCL_2") (pintype "bidirectional"))
    )
    (net (code "55") (name "SDA") (class "Default")
      (node (ref "JP3") (pin "4") (pinfunction "4_4") (pintype "passive"))
      (node (ref "R13") (pin "2") (pinfunction "2_2") (pintype "passive"))
      (node (ref "R35") (pin "1") (pinfunction "1_1") (pintype "passive"))
      (node (ref "U1") (pin "3") (pinfunction "SDI/SDA_3") (pintype "bidirectional"))
      (node (ref "U2") (pin "1") (pinfunction "SDA_1") (pintype "bidirectional"))
    )
    (net (code "56") (name "TXD0") (class "Default")
      (node (ref "JP1") (pin "5") (pinfunction "5_5") (pintype "passive"))
      (node (ref "U4") (pin "35") (pinfunction "TXD0_35") (pintype "bidirectional"))
    )
    (net (code "57") (name "unconnected-(IC1-1_SAFEBOOT_N-Pad1)") (class "Default")
      (node (ref "IC1") (pin "1") (pinfunction "1_SAFEBOOT_N_1") (pintype "bidirectional"))
    )
    (net (code "58") (name "unconnected-(IC1-2_D_SEL-Pad2)") (class "Default")
      (node (ref "IC1") (pin "2") (pinfunction "2_D_SEL_2") (pintype "bidirectional"))
    )
    (net (code "59") (name "unconnected-(IC1-4_EXTINT-Pad4)") (class "Default")
      (node (ref "IC1") (pin "4") (pinfunction "4_EXTINT_4") (pintype "bidirectional"))
    )
    (net (code "60") (name "unconnected-(IC1-5_USB_DM-Pad5)") (class "Default")
      (node (ref "IC1") (pin "5") (pinfunction "5_USB_DM_5") (pintype "bidirectional"))
    )
    (net (code "61") (name "unconnected-(IC1-6_USB_DP-Pad6)") (class "Default")
      (node (ref "IC1") (pin "6") (pinfunction "6_USB_DP_6") (pintype "bidirectional"))
    )
    (net (code "62") (name "unconnected-(IC1-7_VDD_USB-Pad7)") (class "Default")
      (node (ref "IC1") (pin "7") (pinfunction "7_VDD_USB_7") (pintype "bidirectional"))
    )
    (net (code "63") (name "unconnected-(IC1-14_LNA_EN{slash}RESERVED-Pad14)") (class "Default")
      (node (ref "IC1") (pin "14") (pinfunction "14_LNA_EN/RESERVED_14") (pintype "bidirectional"))
    )
    (net (code "64") (name "unconnected-(IC1-15_RESERVED-Pad15)") (class "Default")
      (node (ref "IC1") (pin "15") (pinfunction "15_RESERVED_15") (pintype "bidirectional"))
    )
    (net (code "65") (name "unconnected-(IC1-16_RESERVED-Pad16)") (class "Default")
      (node (ref "IC1") (pin "16") (pinfunction "16_RESERVED_16") (pintype "bidirectional"))
    )
    (net (code "66") (name "unconnected-(IC1-17_RESERVED-Pad17)") (class "Default")
      (node (ref "IC1") (pin "17") (pinfunction "17_RESERVED_17") (pintype "bidirectional"))
    )
    (net (code "67") (name "unconnected-(IC1-18_SDA{slash}SPI_CS_N-Pad18)") (class "Default")
      (node (ref "IC1") (pin "18") (pinfunction "18_SDA/SPI_CS_N_18") (pintype "bidirectional"))
    )
    (net (code "68") (name "unconnected-(IC1-19_SCL{slash}SPI_CLK-Pad19)") (class "Default")
      (node (ref "IC1") (pin "19") (pinfunction "19_SCL/SPI_CLK_19") (pintype "bidirectional"))
    )
    (net (code "69") (name "unconnected-(J1-2DM-Pad2)") (class "Default")
      (node (ref "J1") (pin "2") (pinfunction "2DM_2") (pintype "bidirectional"))
    )
    (net (code "70") (name "unconnected-(J1-3DP-Pad3)") (class "Default")
      (node (ref "J1") (pin "3") (pinfunction "3DP_3") (pintype "bidirectional"))
    )
    (net (code "71") (name "unconnected-(J1-4ID-Pad4)") (class "Default")
      (node (ref "J1") (pin "4") (pinfunction "4ID_4") (pintype "bidirectional"))
    )
    (net (code "72") (name "unconnected-(U3-NC-Pad8)") (class "Default")
      (node (ref "U3") (pin "8") (pinfunction "NC_8") (pintype "bidirectional"))
    )
    (net (code "73") (name "unconnected-(U4-IO21-Pad33)") (class "Default")
      (node (ref "U4") (pin "33") (pinfunction "IO21_33") (pintype "bidirectional"))
    )
    (net (code "74") (name "unconnected-(U4-IO22-Pad36)") (class "Default")
      (node (ref "U4") (pin "36") (pinfunction "IO22_36") (pintype "bidirectional"))
    )
    (net (code "75") (name "unconnected-(U4-IO25-Pad10)") (class "Default")
      (node (ref "U4") (pin "10") (pinfunction "IO25_10") (pintype "bidirectional"))
    )
    (net (code "76") (name "unconnected-(U4-IO26-Pad11)") (class "Default")
      (node (ref "U4") (pin "11") (pinfunction "IO26_11") (pintype "bidirectional"))
    )
    (net (code "77") (name "unconnected-(U4-IO27-Pad12)") (class "Default")
      (node (ref "U4") (pin "12") (pinfunction "IO27_12") (pintype "bidirectional"))
    )
    (net (code "78") (name "unconnected-(U4-IO32-Pad8)") (class "Default")
      (node (ref "U4") (pin "8") (pinfunction "IO32_8") (pintype "bidirectional"))
    )
    (net (code "79") (name "unconnected-(U4-IO33-Pad9)") (class "Default")
      (node (ref "U4") (pin "9") (pinfunction "IO33_9") (pintype "bidirectional"))
    )
    (net (code "80") (name "unconnected-(U4-SCK{slash}CLK-Pad20)") (class "Default")
      (node (ref "U4") (pin "20") (pinfunction "SCK/CLK_20") (pintype "bidirectional"))
    )
    (net (code "81") (name "unconnected-(U4-SCS{slash}CMD-Pad19)") (class "Default")
      (node (ref "U4") (pin "19") (pinfunction "SCS/CMD_19") (pintype "bidirectional"))
    )
    (net (code "82") (name "unconnected-(U4-SDI{slash}SD1-Pad22)") (class "Default")
      (node (ref "U4") (pin "22") (pinfunction "SDI/SD1_22") (pintype "bidirectional"))
    )
    (net (code "83") (name "unconnected-(U4-SDO{slash}SD0-Pad21)") (class "Default")
      (node (ref "U4") (pin "21") (pinfunction "SDO/SD0_21") (pintype "bidirectional"))
    )
    (net (code "84") (name "unconnected-(U4-SHD{slash}SD2-Pad17)") (class "Default")
      (node (ref "U4") (pin "17") (pinfunction "SHD/SD2_17") (pintype "bidirectional"))
    )
    (net (code "85") (name "unconnected-(U4-SWP{slash}SD3-Pad18)") (class "Default")
      (node (ref "U4") (pin "18") (pinfunction "SWP/SD3_18") (pintype "bidirectional"))
    )
  )
)
